# HB-power_v1_3.net
KiCad netlist of a schematic drawn in EAGLE
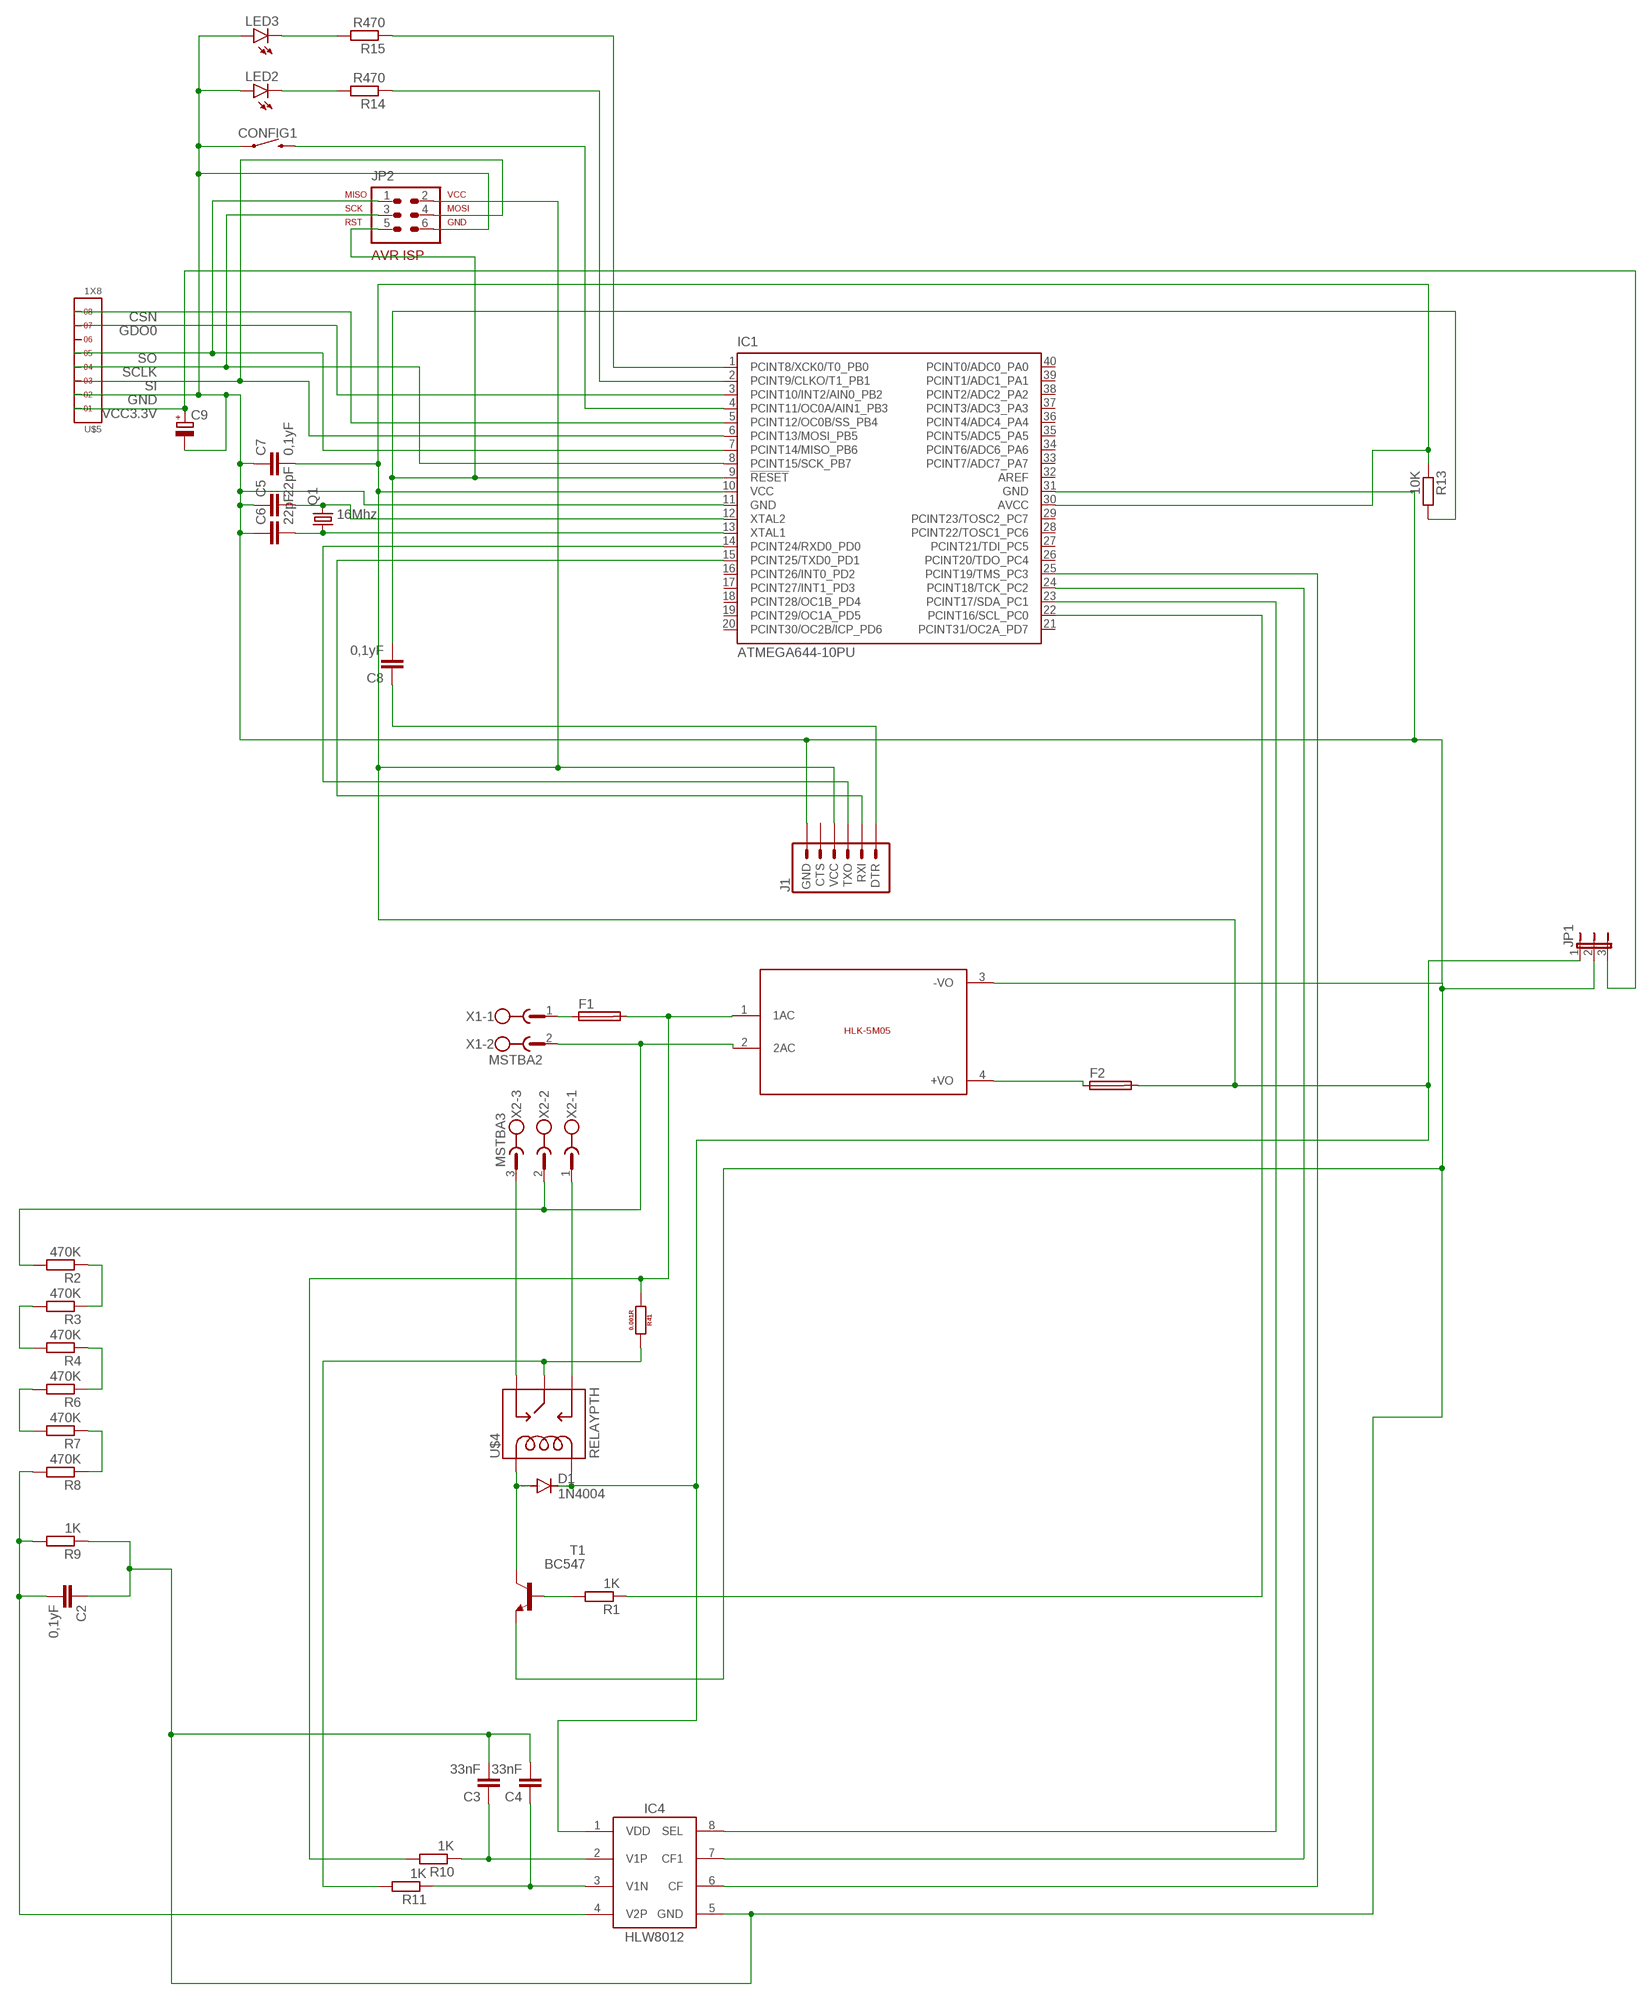
[diagram p0: schematic, sheet 1]

(export (version "E")
  (design (tool "Eeschema 10.0.6"))
  (components
    (comp (ref "C2")
      (value "0,1yF")
      (footprint "eagle-import:C050-024X044")
      (libsource (lib "eagle-import") (part "C-EU050-024X044"))
    )
    (comp (ref "C3")
      (value "33nF")
      (footprint "eagle-import:C050-024X044")
      (libsource (lib "eagle-import") (part "C-EU050-024X044"))
    )
    (comp (ref "C4")
      (value "33nF")
      (footprint "eagle-import:C050-024X044")
      (libsource (lib "eagle-import") (part "C-EU050-024X044"))
    )
    (comp (ref "C5")
      (value "22pF")
      (footprint "eagle-import:C025-024X044")
      (libsource (lib "eagle-import") (part "C-EU025-024X044"))
    )
    (comp (ref "C6")
      (value "22pF")
      (footprint "eagle-import:C025-024X044")
      (libsource (lib "eagle-import") (part "C-EU025-024X044"))
    )
    (comp (ref "C7")
      (value "0,1yF")
      (footprint "eagle-import:C025-024X044")
      (libsource (lib "eagle-import") (part "C-EU025-024X044"))
    )
    (comp (ref "C8")
      (value "0,1yF")
      (footprint "eagle-import:C025-024X044")
      (libsource (lib "eagle-import") (part "C-EU025-024X044"))
    )
    (comp (ref "C9")
      (value "CPOL-EUE2.5-5")
      (footprint "eagle-import:E2,5-5")
      (libsource (lib "eagle-import") (part "CPOL-EUE2.5-5"))
    )
    (comp (ref "CONFIG1")
      (value "MOMENTARY-SWITCH-SPST-PTH-6.0MM-KIT")
      (footprint "eagle-import:TACTILE_SWITCH_PTH_6.0MM_KIT")
      (libsource (lib "eagle-import") (part "MOMENTARY-SWITCH-SPST-PTH-6.0MM-KIT"))
    )
    (comp (ref "D1")
      (value "1N4004")
      (footprint "eagle-import:DO41-10")
      (libsource (lib "eagle-import") (part "1N4004"))
    )
    (comp (ref "F1")
      (value "SH22,5A")
      (footprint "eagle-import:SH22,5A")
      (fields (field (name "MPN") "0031.7701.11"))
      (libsource (lib "eagle-import") (part "SH22,5A"))
    )
    (comp (ref "F2")
      (value "SH22,5A")
      (footprint "eagle-import:SH22,5A")
      (fields (field (name "MPN") "0031.7701.11"))
      (libsource (lib "eagle-import") (part "SH22,5A"))
    )
    (comp (ref "IC1")
      (value "ATMEGA644-10PU")
      (footprint "eagle-import:DIL40")
      (fields (field (name "MPN") "ATMEGA644V-10PU"))
      (libsource (lib "eagle-import") (part "ATMEGA644-PU10"))
    )
    (comp (ref "IC4")
      (value "HLW8012")
      (footprint "eagle-import:SOP8")
      (libsource (lib "eagle-import") (part "HLW8012"))
    )
    (comp (ref "J1")
      (value "6_PIN_SERIAL_TARGETLONGPADS")
      (footprint "eagle-import:1X06_LONGPADS")
      (libsource (lib "eagle-import") (part "6_PIN_SERIAL_TARGETLONGPADS"))
    )
    (comp (ref "JP1")
      (value "JP2E")
      (footprint "eagle-import:JP2")
      (libsource (lib "eagle-import") (part "JP2E"))
    )
    (comp (ref "JP2")
      (value "AVR-ISP-6VERT")
      (footprint "eagle-import:AVR-ISP-6")
      (libsource (lib "eagle-import") (part "AVR-ISP-6VERT"))
    )
    (comp (ref "LED2")
      (value "LED3MM")
      (footprint "eagle-import:LED3MM")
      (libsource (lib "eagle-import") (part "LED3MM"))
    )
    (comp (ref "LED3")
      (value "LED3MM")
      (footprint "eagle-import:LED3MM")
      (libsource (lib "eagle-import") (part "LED3MM"))
    )
    (comp (ref "Q1")
      (value "16Mhz")
      (footprint "eagle-import:HC49U-V")
      (libsource (lib "eagle-import") (part "CRYSTALHC49U-V"))
    )
    (comp (ref "R1")
      (value "1K")
      (footprint "eagle-import:0309_10")
      (libsource (lib "eagle-import") (part "R-EU_0309/10"))
    )
    (comp (ref "R2")
      (value "470K")
      (footprint "eagle-import:0309_10")
      (libsource (lib "eagle-import") (part "R-EU_0309/10"))
    )
    (comp (ref "R3")
      (value "470K")
      (footprint "eagle-import:0309_10")
      (libsource (lib "eagle-import") (part "R-EU_0309/10"))
    )
    (comp (ref "R4")
      (value "470K")
      (footprint "eagle-import:0309_10")
      (libsource (lib "eagle-import") (part "R-EU_0309/10"))
    )
    (comp (ref "R6")
      (value "470K")
      (footprint "eagle-import:0309_10")
      (libsource (lib "eagle-import") (part "R-EU_0309/10"))
    )
    (comp (ref "R7")
      (value "470K")
      (footprint "eagle-import:0309_10")
      (libsource (lib "eagle-import") (part "R-EU_0309/10"))
    )
    (comp (ref "R8")
      (value "470K")
      (footprint "eagle-import:0309_10")
      (libsource (lib "eagle-import") (part "R-EU_0309/10"))
    )
    (comp (ref "R9")
      (value "1K")
      (footprint "eagle-import:0309_10")
      (libsource (lib "eagle-import") (part "R-EU_0309/10"))
    )
    (comp (ref "R10")
      (value "1K")
      (footprint "eagle-import:0309_10")
      (libsource (lib "eagle-import") (part "R-EU_0309/10"))
    )
    (comp (ref "R11")
      (value "1K")
      (footprint "eagle-import:0309_10")
      (libsource (lib "eagle-import") (part "R-EU_0309/10"))
    )
    (comp (ref "R13")
      (value "10K")
      (footprint "eagle-import:0309_10")
      (libsource (lib "eagle-import") (part "R-EU_0309/10"))
    )
    (comp (ref "R14")
      (value "R470")
      (footprint "eagle-import:0309_10")
      (libsource (lib "eagle-import") (part "R-EU_0309/10"))
    )
    (comp (ref "R15")
      (value "R470")
      (footprint "eagle-import:0309_10")
      (libsource (lib "eagle-import") (part "R-EU_0309/10"))
    )
    (comp (ref "R41")
      (value "0.001R")
      (footprint "eagle-import:2512")
      (libsource (lib "eagle-import") (part "RESISTOR2512"))
    )
    (comp (ref "T1")
      (value "BC547")
      (footprint "eagle-import:TO92")
      (libsource (lib "eagle-import") (part "BC547"))
    )
    (comp (ref "U$3")
      (value "5VDC/5W")
      (footprint "eagle-import:HLK-5M05")
      (libsource (lib "eagle-import") (part "HLK-5M05"))
    )
    (comp (ref "U$4")
      (value "RELAYPTH")
      (footprint "eagle-import:SRD-05VDC-SL-C")
      (libsource (lib "eagle-import") (part "RELAYPTH"))
    )
    (comp (ref "U$5")
      (value "1X8")
      (footprint "eagle-import:1X8")
      (libsource (lib "eagle-import") (part "1X8"))
    )
    (comp (ref "X1")
      (value "MSTBA2")
      (footprint "eagle-import:MSTBA2")
      (fields (field (name "MF") "FARNELL") (field (name "MPN") "1757242"))
      (libsource (lib "eagle-import") (part "MSTBA2"))
    )
    (comp (ref "X2")
      (value "MSTBA3")
      (footprint "eagle-import:MSTBA3")
      (fields (field (name "MF") "FARNELL") (field (name "MPN") "1757255"))
      (libsource (lib "eagle-import") (part "MSTBA3"))
    )
  )
  (nets
    (net (code "1") (name "/CSN") (class "Default")
      (node (ref "IC1") (pin "5") (pinfunction "PCINT12/OC0B/SS_PB4_5") (pintype "bidirectional"))
      (node (ref "U$5") (pin "8") (pinfunction "8_8") (pintype "bidirectional"))
    )
    (net (code "2") (name "/GDO0") (class "Default")
      (node (ref "IC1") (pin "3") (pinfunction "PCINT10/INT2/AIN0_PB2_3") (pintype "bidirectional"))
      (node (ref "U$5") (pin "7") (pinfunction "7_7") (pintype "bidirectional"))
    )
    (net (code "3") (name "/GND") (class "Default")
      (node (ref "C2") (pin "1") (pinfunction "1_1") (pintype "passive"))
      (node (ref "C3") (pin "2") (pinfunction "2_2") (pintype "passive"))
      (node (ref "C4") (pin "2") (pinfunction "2_2") (pintype "passive"))
      (node (ref "C5") (pin "1") (pinfunction "1_1") (pintype "passive"))
      (node (ref "C6") (pin "1") (pinfunction "1_1") (pintype "passive"))
      (node (ref "C7") (pin "1") (pinfunction "1_1") (pintype "passive"))
      (node (ref "C9") (pin "-") (pinfunction "-_-") (pintype "passive"))
      (node (ref "CONFIG1") (pin "1") (pinfunction "1_1") (pintype "passive"))
      (node (ref "IC1") (pin "11") (pinfunction "GND_11") (pintype "power_in"))
      (node (ref "IC1") (pin "31") (pinfunction "GND_31") (pintype "power_in"))
      (node (ref "IC4") (pin "5") (pinfunction "GND_5") (pintype "power_in"))
      (node (ref "J1") (pin "6") (pinfunction "GND_6") (pintype "passive"))
      (node (ref "JP1") (pin "2") (pinfunction "2_2") (pintype "passive"))
      (node (ref "JP2") (pin "6") (pinfunction "6_6") (pintype "passive"))
      (node (ref "LED2") (pin "A") (pinfunction "A_A") (pintype "passive"))
      (node (ref "LED3") (pin "A") (pinfunction "A_A") (pintype "passive"))
      (node (ref "R9") (pin "1") (pinfunction "1_1") (pintype "passive"))
      (node (ref "T1") (pin "1") (pinfunction "E_1") (pintype "passive"))
      (node (ref "U$3") (pin "3") (pinfunction "-VO_3") (pintype "bidirectional"))
      (node (ref "U$5") (pin "2") (pinfunction "2_2") (pintype "bidirectional"))
    )
    (net (code "4") (name "/SCLK") (class "Default")
      (node (ref "IC1") (pin "8") (pinfunction "PCINT15/SCK_PB7_8") (pintype "bidirectional"))
      (node (ref "JP2") (pin "3") (pinfunction "3_3") (pintype "passive"))
      (node (ref "U$5") (pin "4") (pinfunction "4_4") (pintype "bidirectional"))
    )
    (net (code "5") (name "/SI") (class "Default")
      (node (ref "IC1") (pin "6") (pinfunction "PCINT13/MOSI_PB5_6") (pintype "bidirectional"))
      (node (ref "JP2") (pin "4") (pinfunction "4_4") (pintype "passive"))
      (node (ref "U$5") (pin "3") (pinfunction "3_3") (pintype "bidirectional"))
    )
    (net (code "6") (name "/SO") (class "Default")
      (node (ref "IC1") (pin "7") (pinfunction "PCINT14/MISO_PB6_7") (pintype "bidirectional"))
      (node (ref "JP2") (pin "1") (pinfunction "1_1") (pintype "passive"))
      (node (ref "U$5") (pin "5") (pinfunction "5_5") (pintype "bidirectional"))
    )
    (net (code "7") (name "/VCC3.3V") (class "Default")
      (node (ref "C9") (pin "+") (pinfunction "+_+") (pintype "passive"))
      (node (ref "JP1") (pin "3") (pinfunction "3_3") (pintype "passive"))
      (node (ref "U$5") (pin "1") (pinfunction "1_1") (pintype "bidirectional"))
    )
    (net (code "8") (name "Net-(CONFIG1-2)") (class "Default")
      (node (ref "CONFIG1") (pin "3") (pinfunction "2_3") (pintype "passive"))
      (node (ref "IC1") (pin "4") (pinfunction "PCINT11/OC0A/AIN1_PB3_4") (pintype "bidirectional"))
    )
    (net (code "9") (name "Net-(F1-Pad1)") (class "Default")
      (node (ref "F1") (pin "1") (pinfunction "1_1") (pintype "passive"))
      (node (ref "X1") (pin "1") (pinfunction "1_1") (pintype "passive"))
    )
    (net (code "10") (name "Net-(IC1-AVCC)") (class "Default")
      (node (ref "C7") (pin "2") (pinfunction "2_2") (pintype "passive"))
      (node (ref "D1") (pin "C") (pinfunction "C_C") (pintype "passive"))
      (node (ref "F2") (pin "2") (pinfunction "2_2") (pintype "passive"))
      (node (ref "IC1") (pin "10") (pinfunction "VCC_10") (pintype "power_in"))
      (node (ref "IC1") (pin "30") (pinfunction "AVCC_30") (pintype "power_in"))
      (node (ref "IC4") (pin "1") (pinfunction "VDD_1") (pintype "power_in"))
      (node (ref "J1") (pin "4") (pinfunction "VCC_4") (pintype "passive"))
      (node (ref "JP1") (pin "1") (pinfunction "1_1") (pintype "passive"))
      (node (ref "JP2") (pin "2") (pinfunction "2_2") (pintype "passive"))
      (node (ref "R13") (pin "1") (pinfunction "1_1") (pintype "passive"))
      (node (ref "U$4") (pin "COIL0") (pinfunction "COIL0_COIL0") (pintype "bidirectional"))
    )
    (net (code "11") (name "Net-(IC1-PCINT8{slash}XCK0{slash}T0_PB0)") (class "Default")
      (node (ref "IC1") (pin "1") (pinfunction "PCINT8/XCK0/T0_PB0_1") (pintype "bidirectional"))
      (node (ref "R15") (pin "1") (pinfunction "1_1") (pintype "passive"))
    )
    (net (code "12") (name "Net-(IC1-PCINT9{slash}CLKO{slash}T1_PB1)") (class "Default")
      (node (ref "IC1") (pin "2") (pinfunction "PCINT9/CLKO/T1_PB1_2") (pintype "bidirectional"))
      (node (ref "R14") (pin "1") (pinfunction "1_1") (pintype "passive"))
    )
    (net (code "13") (name "Net-(IC1-PCINT16{slash}SCL_PC0)") (class "Default")
      (node (ref "IC1") (pin "22") (pinfunction "PCINT16/SCL_PC0_22") (pintype "bidirectional"))
      (node (ref "R1") (pin "1") (pinfunction "1_1") (pintype "passive"))
    )
    (net (code "14") (name "Net-(IC1-PCINT17{slash}SDA_PC1)") (class "Default")
      (node (ref "IC1") (pin "23") (pinfunction "PCINT17/SDA_PC1_23") (pintype "bidirectional"))
      (node (ref "IC4") (pin "8") (pinfunction "SEL_8") (pintype "input"))
    )
    (net (code "15") (name "Net-(IC1-PCINT18{slash}TCK_PC2)") (class "Default")
      (node (ref "IC1") (pin "24") (pinfunction "PCINT18/TCK_PC2_24") (pintype "bidirectional"))
      (node (ref "IC4") (pin "7") (pinfunction "CF1_7") (pintype "output"))
    )
    (net (code "16") (name "Net-(IC1-PCINT19{slash}TMS_PC3)") (class "Default")
      (node (ref "IC1") (pin "25") (pinfunction "PCINT19/TMS_PC3_25") (pintype "bidirectional"))
      (node (ref "IC4") (pin "6") (pinfunction "CF_6") (pintype "output"))
    )
    (net (code "17") (name "Net-(IC1-PCINT24{slash}RXD0_PD0)") (class "Default")
      (node (ref "IC1") (pin "14") (pinfunction "PCINT24/RXD0_PD0_14") (pintype "bidirectional"))
      (node (ref "J1") (pin "3") (pinfunction "TXO_3") (pintype "passive"))
    )
    (net (code "18") (name "Net-(IC1-PCINT25{slash}TXD0_PD1)") (class "Default")
      (node (ref "IC1") (pin "15") (pinfunction "PCINT25/TXD0_PD1_15") (pintype "bidirectional"))
      (node (ref "J1") (pin "2") (pinfunction "RXI_2") (pintype "passive"))
    )
    (net (code "19") (name "Net-(IC1-XTAL1)") (class "Default")
      (node (ref "C6") (pin "2") (pinfunction "2_2") (pintype "passive"))
      (node (ref "IC1") (pin "13") (pinfunction "XTAL1_13") (pintype "input"))
      (node (ref "Q1") (pin "1") (pinfunction "1_1") (pintype "passive"))
    )
    (net (code "20") (name "Net-(IC1-XTAL2)") (class "Default")
      (node (ref "C5") (pin "2") (pinfunction "2_2") (pintype "passive"))
      (node (ref "IC1") (pin "12") (pinfunction "XTAL2_12") (pintype "output"))
      (node (ref "Q1") (pin "2") (pinfunction "2_2") (pintype "passive"))
    )
    (net (code "21") (name "Net-(IC1-~{RESET})") (class "Default")
      (node (ref "C8") (pin "2") (pinfunction "2_2") (pintype "passive"))
      (node (ref "IC1") (pin "9") (pinfunction "~{RESET}_9") (pintype "input"))
      (node (ref "JP2") (pin "5") (pinfunction "5_5") (pintype "passive"))
      (node (ref "R13") (pin "2") (pinfunction "2_2") (pintype "passive"))
    )
    (net (code "22") (name "Net-(IC4-V1N)") (class "Default")
      (node (ref "C4") (pin "1") (pinfunction "1_1") (pintype "passive"))
      (node (ref "IC4") (pin "3") (pinfunction "V1N_3") (pintype "input"))
      (node (ref "R11") (pin "1") (pinfunction "1_1") (pintype "passive"))
    )
    (net (code "23") (name "Net-(IC4-V1P)") (class "Default")
      (node (ref "C3") (pin "1") (pinfunction "1_1") (pintype "passive"))
      (node (ref "IC4") (pin "2") (pinfunction "V1P_2") (pintype "input"))
      (node (ref "R10") (pin "1") (pinfunction "1_1") (pintype "passive"))
    )
    (net (code "24") (name "Net-(IC4-V2P)") (class "Default")
      (node (ref "C2") (pin "2") (pinfunction "2_2") (pintype "passive"))
      (node (ref "IC4") (pin "4") (pinfunction "V2P_4") (pintype "input"))
      (node (ref "R8") (pin "2") (pinfunction "2_2") (pintype "passive"))
      (node (ref "R9") (pin "2") (pinfunction "2_2") (pintype "passive"))
    )
    (net (code "25") (name "Net-(J1-DTR)") (class "Default")
      (node (ref "C8") (pin "1") (pinfunction "1_1") (pintype "passive"))
      (node (ref "J1") (pin "1") (pinfunction "DTR_1") (pintype "passive"))
    )
    (net (code "26") (name "Net-(LED2-C)") (class "Default")
      (node (ref "LED2") (pin "K") (pinfunction "C_K") (pintype "passive"))
      (node (ref "R14") (pin "2") (pinfunction "2_2") (pintype "passive"))
    )
    (net (code "27") (name "Net-(LED3-C)") (class "Default")
      (node (ref "LED3") (pin "K") (pinfunction "C_K") (pintype "passive"))
      (node (ref "R15") (pin "2") (pinfunction "2_2") (pintype "passive"))
    )
    (net (code "28") (name "Net-(R2-Pad1)") (class "Default")
      (node (ref "R2") (pin "1") (pinfunction "1_1") (pintype "passive"))
      (node (ref "R3") (pin "1") (pinfunction "1_1") (pintype "passive"))
    )
    (net (code "29") (name "Net-(R3-Pad2)") (class "Default")
      (node (ref "R3") (pin "2") (pinfunction "2_2") (pintype "passive"))
      (node (ref "R4") (pin "2") (pinfunction "2_2") (pintype "passive"))
    )
    (net (code "30") (name "Net-(R4-Pad1)") (class "Default")
      (node (ref "R4") (pin "1") (pinfunction "1_1") (pintype "passive"))
      (node (ref "R6") (pin "1") (pinfunction "1_1") (pintype "passive"))
    )
    (net (code "31") (name "Net-(R6-Pad2)") (class "Default")
      (node (ref "R6") (pin "2") (pinfunction "2_2") (pintype "passive"))
      (node (ref "R7") (pin "2") (pinfunction "2_2") (pintype "passive"))
    )
    (net (code "32") (name "Net-(R7-Pad1)") (class "Default")
      (node (ref "R7") (pin "1") (pinfunction "1_1") (pintype "passive"))
      (node (ref "R8") (pin "1") (pinfunction "1_1") (pintype "passive"))
    )
    (net (code "33") (name "Net-(R11-Pad2)") (class "Default")
      (node (ref "R11") (pin "2") (pinfunction "2_2") (pintype "passive"))
      (node (ref "R41") (pin "2") (pinfunction "2_2") (pintype "passive"))
      (node (ref "U$4") (pin "SWCOMMON") (pinfunction "SWCOMMON_SWCOMMON") (pintype "bidirectional"))
    )
    (net (code "34") (name "Net-(T1-B)") (class "Default")
      (node (ref "R1") (pin "2") (pinfunction "2_2") (pintype "passive"))
      (node (ref "T1") (pin "2") (pinfunction "B_2") (pintype "passive"))
    )
    (net (code "35") (name "Net-(T1-C)") (class "Default")
      (node (ref "D1") (pin "A") (pinfunction "A_A") (pintype "passive"))
      (node (ref "T1") (pin "3") (pinfunction "C_3") (pintype "passive"))
      (node (ref "U$4") (pin "COIL1") (pinfunction "COIL1_COIL1") (pintype "bidirectional"))
    )
    (net (code "36") (name "Net-(U$3-+VO)") (class "Default")
      (node (ref "F2") (pin "1") (pinfunction "1_1") (pintype "passive"))
      (node (ref "U$3") (pin "4") (pinfunction "+VO_4") (pintype "bidirectional"))
    )
    (net (code "37") (name "Net-(U$3-1AC)") (class "Default")
      (node (ref "F1") (pin "2") (pinfunction "2_2") (pintype "passive"))
      (node (ref "R10") (pin "2") (pinfunction "2_2") (pintype "passive"))
      (node (ref "R41") (pin "1") (pinfunction "1_1") (pintype "passive"))
      (node (ref "U$3") (pin "1") (pinfunction "1AC_1") (pintype "bidirectional"))
    )
    (net (code "38") (name "Net-(U$3-2AC)") (class "Default")
      (node (ref "R2") (pin "2") (pinfunction "2_2") (pintype "passive"))
      (node (ref "U$3") (pin "2") (pinfunction "2AC_2") (pintype "bidirectional"))
      (node (ref "X1") (pin "2") (pinfunction "1_2") (pintype "passive"))
      (node (ref "X2") (pin "2") (pinfunction "1_2") (pintype "passive"))
    )
    (net (code "39") (name "Net-(U$4-PadSWOPEN)") (class "Default")
      (node (ref "U$4") (pin "SWOPEN") (pinfunction "SWOPEN_SWOPEN") (pintype "bidirectional"))
      (node (ref "X2") (pin "1") (pinfunction "1_1") (pintype "passive"))
    )
    (net (code "40") (name "Net-(U$4-SWCLOSE)") (class "Default")
      (node (ref "U$4") (pin "SWCLOSED") (pinfunction "SWCLOSE_SWCLOSED") (pintype "bidirectional"))
      (node (ref "X2") (pin "3") (pinfunction "1_3") (pintype "passive"))
    )
    (net (code "41") (name "unconnected-(IC1-AREF-Pad32)") (class "Default")
      (node (ref "IC1") (pin "32") (pinfunction "AREF_32") (pintype "passive"))
    )
    (net (code "42") (name "unconnected-(IC1-PCINT0{slash}ADC0_PA0-Pad40)") (class "Default")
      (node (ref "IC1") (pin "40") (pinfunction "PCINT0/ADC0_PA0_40") (pintype "bidirectional"))
    )
    (net (code "43") (name "unconnected-(IC1-PCINT1{slash}ADC1_PA1-Pad39)") (class "Default")
      (node (ref "IC1") (pin "39") (pinfunction "PCINT1/ADC1_PA1_39") (pintype "bidirectional"))
    )
    (net (code "44") (name "unconnected-(IC1-PCINT2{slash}ADC2_PA2-Pad38)") (class "Default")
      (node (ref "IC1") (pin "38") (pinfunction "PCINT2/ADC2_PA2_38") (pintype "bidirectional"))
    )
    (net (code "45") (name "unconnected-(IC1-PCINT3{slash}ADC3_PA3-Pad37)") (class "Default")
      (node (ref "IC1") (pin "37") (pinfunction "PCINT3/ADC3_PA3_37") (pintype "bidirectional"))
    )
    (net (code "46") (name "unconnected-(IC1-PCINT4{slash}ADC4_PA4-Pad36)") (class "Default")
      (node (ref "IC1") (pin "36") (pinfunction "PCINT4/ADC4_PA4_36") (pintype "bidirectional"))
    )
    (net (code "47") (name "unconnected-(IC1-PCINT5{slash}ADC5_PA5-Pad35)") (class "Default")
      (node (ref "IC1") (pin "35") (pinfunction "PCINT5/ADC5_PA5_35") (pintype "bidirectional"))
    )
    (net (code "48") (name "unconnected-(IC1-PCINT6{slash}ADC6_PA6-Pad34)") (class "Default")
      (node (ref "IC1") (pin "34") (pinfunction "PCINT6/ADC6_PA6_34") (pintype "bidirectional"))
    )
    (net (code "49") (name "unconnected-(IC1-PCINT7{slash}ADC7_PA7-Pad33)") (class "Default")
      (node (ref "IC1") (pin "33") (pinfunction "PCINT7/ADC7_PA7_33") (pintype "bidirectional"))
    )
    (net (code "50") (name "unconnected-(IC1-PCINT20{slash}TDO_PC4-Pad26)") (class "Default")
      (node (ref "IC1") (pin "26") (pinfunction "PCINT20/TDO_PC4_26") (pintype "bidirectional"))
    )
    (net (code "51") (name "unconnected-(IC1-PCINT21{slash}TDI_PC5-Pad27)") (class "Default")
      (node (ref "IC1") (pin "27") (pinfunction "PCINT21/TDI_PC5_27") (pintype "bidirectional"))
    )
    (net (code "52") (name "unconnected-(IC1-PCINT22{slash}TOSC1_PC6-Pad28)") (class "Default")
      (node (ref "IC1") (pin "28") (pinfunction "PCINT22/TOSC1_PC6_28") (pintype "bidirectional"))
    )
    (net (code "53") (name "unconnected-(IC1-PCINT23{slash}TOSC2_PC7-Pad29)") (class "Default")
      (node (ref "IC1") (pin "29") (pinfunction "PCINT23/TOSC2_PC7_29") (pintype "bidirectional"))
    )
    (net (code "54") (name "unconnected-(IC1-PCINT26{slash}INT0_PD2-Pad16)") (class "Default")
      (node (ref "IC1") (pin "16") (pinfunction "PCINT26/INT0_PD2_16") (pintype "bidirectional"))
    )
    (net (code "55") (name "unconnected-(IC1-PCINT27{slash}INT1_PD3-Pad17)") (class "Default")
      (node (ref "IC1") (pin "17") (pinfunction "PCINT27/INT1_PD3_17") (pintype "bidirectional"))
    )
    (net (code "56") (name "unconnected-(IC1-PCINT28{slash}OC1B_PD4-Pad18)") (class "Default")
      (node (ref "IC1") (pin "18") (pinfunction "PCINT28/OC1B_PD4_18") (pintype "bidirectional"))
    )
    (net (code "57") (name "unconnected-(IC1-PCINT29{slash}OC1A_PD5-Pad19)") (class "Default")
      (node (ref "IC1") (pin "19") (pinfunction "PCINT29/OC1A_PD5_19") (pintype "bidirectional"))
    )
    (net (code "58") (name "unconnected-(IC1-PCINT30{slash}OC2B{slash}ICP_PD6-Pad20)") (class "Default")
      (node (ref "IC1") (pin "20") (pinfunction "PCINT30/OC2B/ICP_PD6_20") (pintype "bidirectional"))
    )
    (net (code "59") (name "unconnected-(IC1-PCINT31{slash}OC2A_PD7-Pad21)") (class "Default")
      (node (ref "IC1") (pin "21") (pinfunction "PCINT31/OC2A_PD7_21") (pintype "bidirectional"))
    )
    (net (code "60") (name "unconnected-(J1-CTS-Pad5)") (class "Default")
      (node (ref "J1") (pin "5") (pinfunction "CTS_5") (pintype "passive"))
    )
    (net (code "61") (name "unconnected-(U$5-Pad6)") (class "Default")
      (node (ref "U$5") (pin "6") (pinfunction "6_6") (pintype "bidirectional"))
    )
  )
)
